# fpga-serdes-inside.net
KiCad netlist of a schematic drawn in Altium Designer
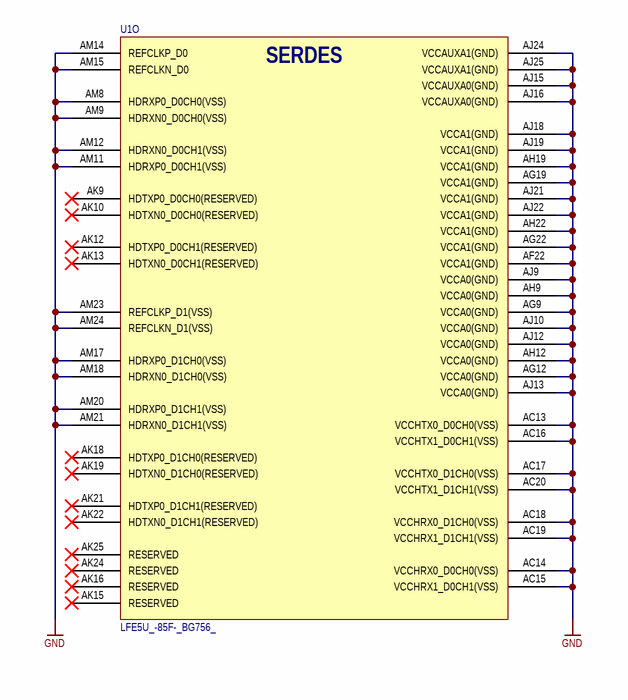
[diagram p0: fpga-serdes-inside.SchDoc]

(export (version "E")
  (design (tool "Eeschema 10.0.6"))
  (components
    (comp (ref "U1")
      (value "LFE5U_-85F-_BG756_")
      (footprint "lattice:caBGA756")
      (description "ECP5 FPGA, 85k LUT, 756-caBGA")
      (fields (field (name "MANUFACTURER") "Lattice Semiconductor"))
      (libsource (lib "lattice") (part "LFE5U_-85F-_BG756_"))
    )
  )
  (nets
    (net (code "1") (name "GND") (class "Default")
      (node (ref "U1") (pin "AC13") (pinfunction "VCCHTX0_D0CH0(VSS)_AC13") (pintype "power_in"))
      (node (ref "U1") (pin "AC14") (pinfunction "VCCHRX0_D0CH0(VSS)_AC14") (pintype "power_in"))
      (node (ref "U1") (pin "AC15") (pinfunction "VCCHRX1_D0CH1(VSS)_AC15") (pintype "power_in"))
      (node (ref "U1") (pin "AC16") (pinfunction "VCCHTX1_D0CH1(VSS)_AC16") (pintype "power_in"))
      (node (ref "U1") (pin "AC17") (pinfunction "VCCHTX0_D1CH0(VSS)_AC17") (pintype "power_in"))
      (node (ref "U1") (pin "AC18") (pinfunction "VCCHRX0_D1CH0(VSS)_AC18") (pintype "power_in"))
      (node (ref "U1") (pin "AC19") (pinfunction "VCCHRX1_D1CH1(VSS)_AC19") (pintype "power_in"))
      (node (ref "U1") (pin "AC20") (pinfunction "VCCHTX1_D1CH1(VSS)_AC20") (pintype "power_in"))
      (node (ref "U1") (pin "AF22") (pinfunction "VCCA1(GND)_AF22") (pintype "power_in"))
      (node (ref "U1") (pin "AG12") (pinfunction "VCCA0(GND)_AG12") (pintype "power_in"))
      (node (ref "U1") (pin "AG19") (pinfunction "VCCA1(GND)_AG19") (pintype "power_in"))
      (node (ref "U1") (pin "AG22") (pinfunction "VCCA1(GND)_AG22") (pintype "power_in"))
      (node (ref "U1") (pin "AG9") (pinfunction "VCCA0(GND)_AG9") (pintype "power_in"))
      (node (ref "U1") (pin "AH12") (pinfunction "VCCA0(GND)_AH12") (pintype "power_in"))
      (node (ref "U1") (pin "AH19") (pinfunction "VCCA1(GND)_AH19") (pintype "power_in"))
      (node (ref "U1") (pin "AH22") (pinfunction "VCCA1(GND)_AH22") (pintype "power_in"))
      (node (ref "U1") (pin "AH9") (pinfunction "VCCA0(GND)_AH9") (pintype "power_in"))
      (node (ref "U1") (pin "AJ10") (pinfunction "VCCA0(GND)_AJ10") (pintype "power_in"))
      (node (ref "U1") (pin "AJ12") (pinfunction "VCCA0(GND)_AJ12") (pintype "power_in"))
      (node (ref "U1") (pin "AJ13") (pinfunction "VCCA0(GND)_AJ13") (pintype "power_in"))
      (node (ref "U1") (pin "AJ15") (pinfunction "VCCAUXA0(GND)_AJ15") (pintype "power_in"))
      (node (ref "U1") (pin "AJ16") (pinfunction "VCCAUXA0(GND)_AJ16") (pintype "power_in"))
      (node (ref "U1") (pin "AJ18") (pinfunction "VCCA1(GND)_AJ18") (pintype "power_in"))
      (node (ref "U1") (pin "AJ19") (pinfunction "VCCA1(GND)_AJ19") (pintype "power_in"))
      (node (ref "U1") (pin "AJ21") (pinfunction "VCCA1(GND)_AJ21") (pintype "power_in"))
      (node (ref "U1") (pin "AJ22") (pinfunction "VCCA1(GND)_AJ22") (pintype "power_in"))
      (node (ref "U1") (pin "AJ24") (pinfunction "VCCAUXA1(GND)_AJ24") (pintype "power_in"))
      (node (ref "U1") (pin "AJ25") (pinfunction "VCCAUXA1(GND)_AJ25") (pintype "power_in"))
      (node (ref "U1") (pin "AJ9") (pinfunction "VCCA0(GND)_AJ9") (pintype "power_in"))
      (node (ref "U1") (pin "AM11") (pinfunction "HDRXP0_D0CH1(VSS)_AM11") (pintype "passive"))
      (node (ref "U1") (pin "AM12") (pinfunction "HDRXN0_D0CH1(VSS)_AM12") (pintype "passive"))
      (node (ref "U1") (pin "AM14") (pinfunction "REFCLKP_D0_AM14") (pintype "passive"))
      (node (ref "U1") (pin "AM15") (pinfunction "REFCLKN_D0_AM15") (pintype "passive"))
      (node (ref "U1") (pin "AM17") (pinfunction "HDRXP0_D1CH0(VSS)_AM17") (pintype "passive"))
      (node (ref "U1") (pin "AM18") (pinfunction "HDRXN0_D1CH0(VSS)_AM18") (pintype "passive"))
      (node (ref "U1") (pin "AM20") (pinfunction "HDRXP0_D1CH1(VSS)_AM20") (pintype "passive"))
      (node (ref "U1") (pin "AM21") (pinfunction "HDRXN0_D1CH1(VSS)_AM21") (pintype "passive"))
      (node (ref "U1") (pin "AM23") (pinfunction "REFCLKP_D1(VSS)_AM23") (pintype "passive"))
      (node (ref "U1") (pin "AM24") (pinfunction "REFCLKN_D1(VSS)_AM24") (pintype "passive"))
      (node (ref "U1") (pin "AM8") (pinfunction "HDRXP0_D0CH0(VSS)_AM8") (pintype "passive"))
      (node (ref "U1") (pin "AM9") (pinfunction "HDRXN0_D0CH0(VSS)_AM9") (pintype "passive"))
    )
    (net (code "2") (name "unconnected-(U1O-HDTXN0_D0CH0(RESERVED)-PadAK10)") (class "Default")
      (node (ref "U1") (pin "AK10") (pinfunction "HDTXN0_D0CH0(RESERVED)_AK10") (pintype "passive+no_connect"))
    )
    (net (code "3") (name "unconnected-(U1O-HDTXN0_D0CH1(RESERVED)-PadAK13)") (class "Default")
      (node (ref "U1") (pin "AK13") (pinfunction "HDTXN0_D0CH1(RESERVED)_AK13") (pintype "passive+no_connect"))
    )
    (net (code "4") (name "unconnected-(U1O-HDTXN0_D1CH0(RESERVED)-PadAK19)") (class "Default")
      (node (ref "U1") (pin "AK19") (pinfunction "HDTXN0_D1CH0(RESERVED)_AK19") (pintype "passive+no_connect"))
    )
    (net (code "5") (name "unconnected-(U1O-HDTXN0_D1CH1(RESERVED)-PadAK22)") (class "Default")
      (node (ref "U1") (pin "AK22") (pinfunction "HDTXN0_D1CH1(RESERVED)_AK22") (pintype "passive+no_connect"))
    )
    (net (code "6") (name "unconnected-(U1O-HDTXP0_D0CH0(RESERVED)-PadAK9)") (class "Default")
      (node (ref "U1") (pin "AK9") (pinfunction "HDTXP0_D0CH0(RESERVED)_AK9") (pintype "passive+no_connect"))
    )
    (net (code "7") (name "unconnected-(U1O-HDTXP0_D0CH1(RESERVED)-PadAK12)") (class "Default")
      (node (ref "U1") (pin "AK12") (pinfunction "HDTXP0_D0CH1(RESERVED)_AK12") (pintype "passive+no_connect"))
    )
    (net (code "8") (name "unconnected-(U1O-HDTXP0_D1CH0(RESERVED)-PadAK18)") (class "Default")
      (node (ref "U1") (pin "AK18") (pinfunction "HDTXP0_D1CH0(RESERVED)_AK18") (pintype "passive+no_connect"))
    )
    (net (code "9") (name "unconnected-(U1O-HDTXP0_D1CH1(RESERVED)-PadAK21)") (class "Default")
      (node (ref "U1") (pin "AK21") (pinfunction "HDTXP0_D1CH1(RESERVED)_AK21") (pintype "passive+no_connect"))
    )
    (net (code "10") (name "unconnected-(U1O-RESERVED-PadAK15)") (class "Default")
      (node (ref "U1") (pin "AK15") (pinfunction "RESERVED_AK15") (pintype "passive+no_connect"))
    )
    (net (code "11") (name "unconnected-(U1O-RESERVED-PadAK16)") (class "Default")
      (node (ref "U1") (pin "AK16") (pinfunction "RESERVED_AK16") (pintype "passive+no_connect"))
    )
    (net (code "12") (name "unconnected-(U1O-RESERVED-PadAK24)") (class "Default")
      (node (ref "U1") (pin "AK24") (pinfunction "RESERVED_AK24") (pintype "passive+no_connect"))
    )
    (net (code "13") (name "unconnected-(U1O-RESERVED-PadAK25)") (class "Default")
      (node (ref "U1") (pin "AK25") (pinfunction "RESERVED_AK25") (pintype "passive+no_connect"))
    )
  )
)
